# 3_power.net
KiCad netlist of a schematic drawn in Altium Designer
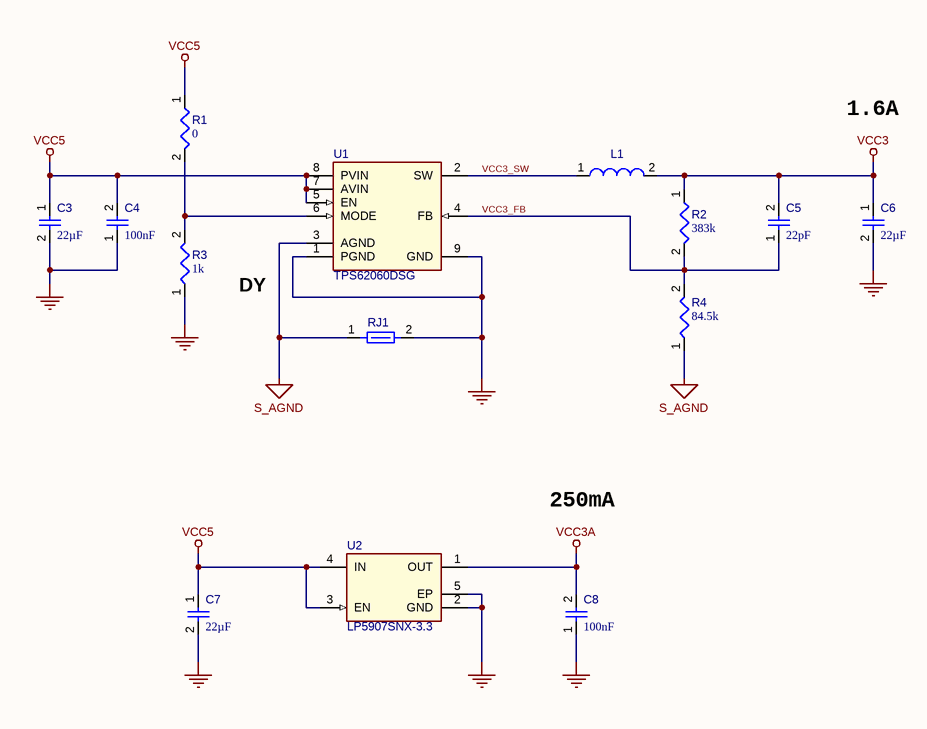
[diagram p0: 3_power.SchDoc]

(export (version "E")
  (design (tool "Eeschema 10.0.6"))
  (components
    (comp (ref "C3")
      (value "22µF")
      (footprint "CAPC0805(2012)145_L")
      (description "Chip Capacitor, 22µF +/-40%, 16V, 0805, Thickness 1.45 mm")
      (fields (field (name "TOLERANCE") "5%") (field (name "Comment") "Capacitor 22µF +/-40% 16V 0805"))
      (libsource (lib "<Company> Server") (part "CAP-NP-2"))
    )
    (comp (ref "C4")
      (value "100nF")
      (footprint "CAPC0402(1005)60_L")
      (description "Chip Capacitor, 100nF +/-20%, 10V, 0402, Thickness 0.6 mm")
      (fields (field (name "TOLERANCE") "20%") (field (name "Comment") "Capacitor 100nF +/-20% 10V 0402"))
      (libsource (lib "<Company> Server") (part "CAP-NP-2"))
    )
    (comp (ref "C5")
      (value "22pF")
      (footprint "CAPC0402(1005)60_L")
      (description "Chip Capacitor, 22pF +/-10%, 50V, 0402, Thickness 0.6 mm")
      (fields (field (name "TOLERANCE") "10%") (field (name "Comment") "Capacitor 22pF +/-10% 50V 0402"))
      (libsource (lib "<Company> Server") (part "CAP-NP-2"))
    )
    (comp (ref "C6")
      (value "22µF")
      (footprint "CAPC0805(2012)145_L")
      (description "Chip Capacitor, 22µF +/-40%, 16V, 0805, Thickness 1.45 mm")
      (fields (field (name "TOLERANCE") "5%") (field (name "Comment") "Capacitor 22µF +/-40% 16V 0805"))
      (libsource (lib "<Company> Server") (part "CAP-NP-2"))
    )
    (comp (ref "C7")
      (value "22µF")
      (footprint "CAPC0805(2012)145_L")
      (description "Chip Capacitor, 22µF +/-40%, 16V, 0805, Thickness 1.45 mm")
      (fields (field (name "TOLERANCE") "5%") (field (name "Comment") "Capacitor 22µF +/-40% 16V 0805"))
      (libsource (lib "<Company> Server") (part "CAP-NP-2"))
    )
    (comp (ref "C8")
      (value "100nF")
      (footprint "CAPC0402(1005)60_L")
      (description "Chip Capacitor, 100nF +/-20%, 10V, 0402, Thickness 0.6 mm")
      (fields (field (name "TOLERANCE") "20%") (field (name "Comment") "Capacitor 100nF +/-20% 10V 0402"))
      (libsource (lib "<Company> Server") (part "CAP-NP-2"))
    )
    (comp (ref "L1")
      (value "VLS252010HBX-2R2M-1")
      (footprint "TDK-VLS252010_V")
      (description "Inductor for Power Circuit, 2.2 uH, +/- 20%, -40 to 105 degC, 2-Pin SMD, RoHS, Tape and Reel")
      (fields (field (name "TOLERANCE") "20%"))
      (libsource (lib "<Company> Server") (part "CMP-001-0020-1"))
    )
    (comp (ref "R1")
      (value "0")
      (footprint "RESC0402(1005)_L")
      (description "Jumper 0402")
      (libsource (lib "<Company> Server") (part "RES-2"))
    )
    (comp (ref "R2")
      (value "383k")
      (footprint "RESC0402(1005)_L")
      (description "Chip Resistor, 383 kOhms, +/-1 %, 63 mW, -55 to 155 degC, 0402")
      (fields (field (name "TOLERANCE") "1%") (field (name "POWER") "63mW"))
      (libsource (lib "<Company> Server") (part "RES-2"))
    )
    (comp (ref "R3")
      (value "1k")
      (footprint "RESC0402(1005)_L")
      (description "Chip Resistor, 1 kOhms, +/-5 %, 63 mW, -55 to 155 degC, 0402")
      (fields (field (name "TOLERANCE") "5%") (field (name "POWER") "63mW"))
      (libsource (lib "<Company> Server") (part "RES-2"))
    )
    (comp (ref "R4")
      (value "84.5k")
      (footprint "RESC0402(1005)_L")
      (description "Chip Resistor, 84,5 kOhms, +/-1 %, 63 mW, -55 to 155 degC, 0402")
      (fields (field (name "TOLERANCE") "1%") (field (name "POWER") "63mW"))
      (libsource (lib "<Company> Server") (part "RES-2"))
    )
    (comp (ref "RJ1")
      (value "Net Tie 10x8mil")
      (footprint "New footprint 1")
      (libsource (lib "<Company> Server") (part "CMP-00022-00002-2"))
    )
    (comp (ref "U1")
      (value "TPS62060DSG")
      (footprint "DSG0008A_V")
      (description "Step Down Converter, 3 MHz, 1.6 A, -45 to 85 degC, 8-Pin WSON, RoHS, Tape and Reel")
      (libsource (lib "<Company> Server") (part "CMP-00002-13_2"))
    )
    (comp (ref "U2")
      (value "LP5907SNX-3.3")
      (footprint "TI-DQN4-480X480TP_V")
      (description "Ultra-Low-Noise, Low-IQ LDO, 3.3 V, 0.25 A, -40 to 125 degC, 4-Pin X2SON, RoHS, Tape and Reel")
      (libsource (lib "<Company> Server") (part "CMP-00094-7"))
    )
  )
  (nets
    (net (code "1") (name "/VCC3_FB") (class "Default")
      (node (ref "C5") (pin "1") (pinfunction "1_1") (pintype "passive"))
      (node (ref "R2") (pin "2") (pinfunction "2_2") (pintype "passive"))
      (node (ref "R4") (pin "2") (pinfunction "2_2") (pintype "passive"))
      (node (ref "U1") (pin "4") (pinfunction "FB_4") (pintype "input"))
    )
    (net (code "2") (name "/VCC3_SW") (class "Default")
      (node (ref "L1") (pin "1") (pinfunction "1_1") (pintype "passive"))
      (node (ref "U1") (pin "2") (pinfunction "SW_2") (pintype "power_in"))
    )
    (net (code "3") (name "GND") (class "Default")
      (node (ref "C3") (pin "2") (pinfunction "2_2") (pintype "passive"))
      (node (ref "C4") (pin "1") (pinfunction "1_1") (pintype "passive"))
      (node (ref "C6") (pin "2") (pinfunction "2_2") (pintype "passive"))
      (node (ref "C7") (pin "2") (pinfunction "2_2") (pintype "passive"))
      (node (ref "C8") (pin "1") (pinfunction "1_1") (pintype "passive"))
      (node (ref "R3") (pin "1") (pinfunction "1_1") (pintype "passive"))
      (node (ref "RJ1") (pin "2") (pinfunction "2_2") (pintype "passive"))
      (node (ref "U1") (pin "1") (pinfunction "PGND_1") (pintype "power_in"))
      (node (ref "U1") (pin "9") (pinfunction "GND_9") (pintype "power_in"))
      (node (ref "U2") (pin "2") (pinfunction "GND_2") (pintype "power_in"))
      (node (ref "U2") (pin "5") (pinfunction "EP_5") (pintype "power_in"))
    )
    (net (code "4") (name "Net-(U1-MODE)") (class "Default")
      (node (ref "R1") (pin "2") (pinfunction "2_2") (pintype "passive"))
      (node (ref "R3") (pin "2") (pinfunction "2_2") (pintype "passive"))
      (node (ref "U1") (pin "6") (pinfunction "MODE_6") (pintype "input"))
    )
    (net (code "5") (name "S_AGND") (class "Default")
      (node (ref "R4") (pin "1") (pinfunction "1_1") (pintype "passive"))
      (node (ref "RJ1") (pin "1") (pinfunction "1_1") (pintype "passive"))
      (node (ref "U1") (pin "3") (pinfunction "AGND_3") (pintype "power_in"))
    )
    (net (code "6") (name "VCC3") (class "Default")
      (node (ref "C5") (pin "2") (pinfunction "2_2") (pintype "passive"))
      (node (ref "C6") (pin "1") (pinfunction "1_1") (pintype "passive"))
      (node (ref "L1") (pin "2") (pinfunction "2_2") (pintype "passive"))
      (node (ref "R2") (pin "1") (pinfunction "1_1") (pintype "passive"))
    )
    (net (code "7") (name "VCC3A") (class "Default")
      (node (ref "C8") (pin "2") (pinfunction "2_2") (pintype "passive"))
      (node (ref "U2") (pin "1") (pinfunction "OUT_1") (pintype "power_in"))
    )
    (net (code "8") (name "VCC5") (class "Default")
      (node (ref "C3") (pin "1") (pinfunction "1_1") (pintype "passive"))
      (node (ref "C4") (pin "2") (pinfunction "2_2") (pintype "passive"))
      (node (ref "C7") (pin "1") (pinfunction "1_1") (pintype "passive"))
      (node (ref "R1") (pin "1") (pinfunction "1_1") (pintype "passive"))
      (node (ref "U1") (pin "5") (pinfunction "EN_5") (pintype "input"))
      (node (ref "U1") (pin "7") (pinfunction "AVIN_7") (pintype "power_in"))
      (node (ref "U1") (pin "8") (pinfunction "PVIN_8") (pintype "power_in"))
      (node (ref "U2") (pin "3") (pinfunction "EN_3") (pintype "input"))
      (node (ref "U2") (pin "4") (pinfunction "IN_4") (pintype "power_in"))
    )
  )
)
